# Extrudrboard2.net
KiCad netlist of a schematic drawn in EAGLE
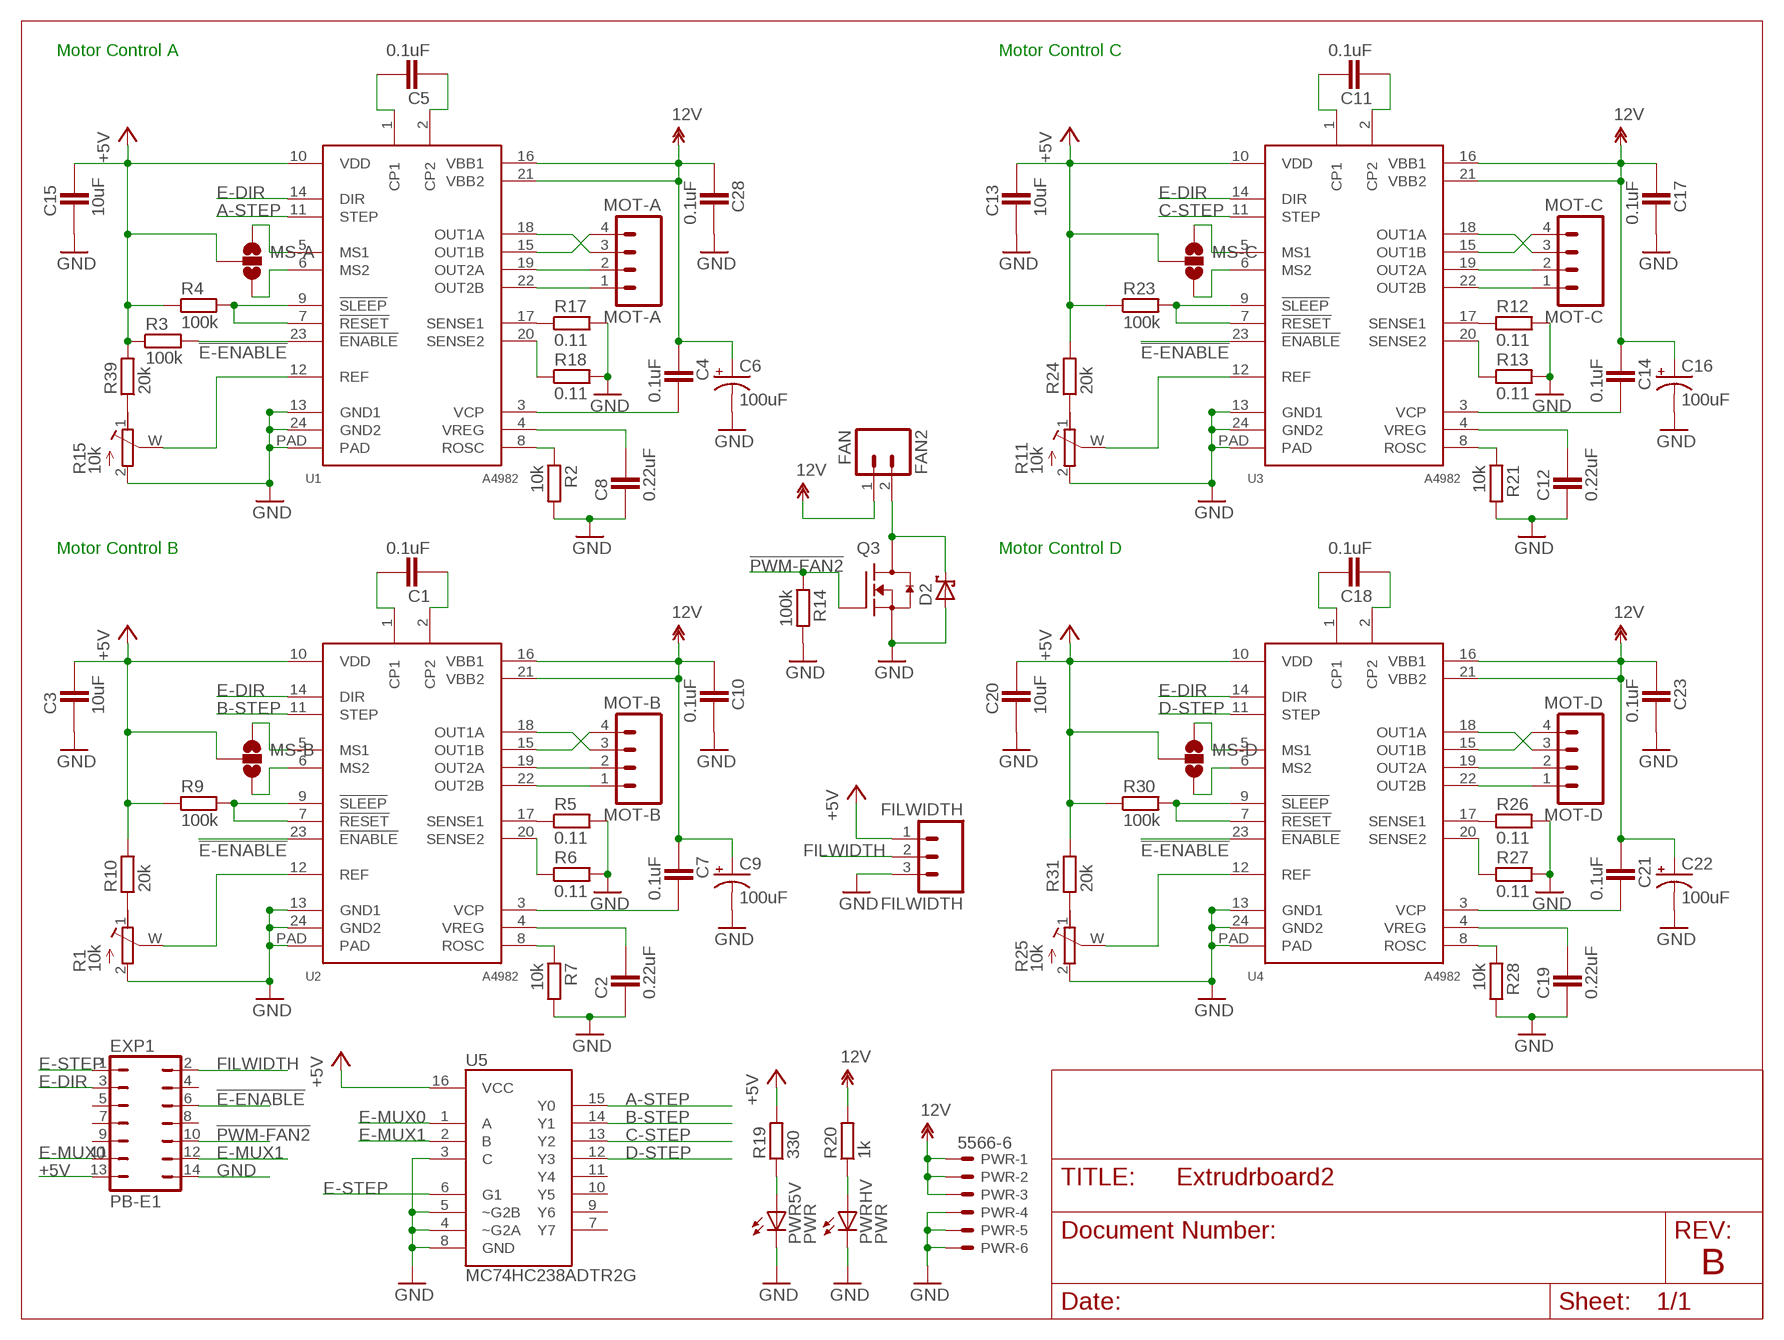
[diagram p0: schematic, sheet 1]

(export (version "E")
  (design (tool "Eeschema 10.0.6"))
  (components
    (comp (ref "C1")
      (value "0.1uF")
      (footprint "eagle-import:CAPC2012X145AN")
      (libsource (lib "eagle-import") (part "CAPACITOR_0805"))
    )
    (comp (ref "C2")
      (value "0.22uF")
      (footprint "eagle-import:CAPC2012X145AN")
      (libsource (lib "eagle-import") (part "CAPACITOR_0805"))
    )
    (comp (ref "C3")
      (value "10uF")
      (footprint "eagle-import:CAPC2012X145AN")
      (libsource (lib "eagle-import") (part "CAPACITOR_0805"))
    )
    (comp (ref "C4")
      (value "0.1uF")
      (footprint "eagle-import:CAPC2012X145AN")
      (libsource (lib "eagle-import") (part "CAPACITOR_0805"))
    )
    (comp (ref "C5")
      (value "0.1uF")
      (footprint "eagle-import:CAPC2012X145AN")
      (libsource (lib "eagle-import") (part "CAPACITOR_0805"))
    )
    (comp (ref "C6")
      (value "100uF")
      (footprint "eagle-import:PANASONIC_D")
      (libsource (lib "eagle-import") (part "CPOL-USD"))
    )
    (comp (ref "C7")
      (value "0.1uF")
      (footprint "eagle-import:CAPC2012X145AN")
      (libsource (lib "eagle-import") (part "CAPACITOR_0805"))
    )
    (comp (ref "C8")
      (value "0.22uF")
      (footprint "eagle-import:CAPC2012X145AN")
      (libsource (lib "eagle-import") (part "CAPACITOR_0805"))
    )
    (comp (ref "C9")
      (value "100uF")
      (footprint "eagle-import:PANASONIC_D")
      (libsource (lib "eagle-import") (part "CPOL-USD"))
    )
    (comp (ref "C10")
      (value "0.1uF")
      (footprint "eagle-import:CAPC2012X145AN")
      (libsource (lib "eagle-import") (part "CAPACITOR_0805"))
    )
    (comp (ref "C11")
      (value "0.1uF")
      (footprint "eagle-import:CAPC2012X145AN")
      (libsource (lib "eagle-import") (part "CAPACITOR_0805"))
    )
    (comp (ref "C12")
      (value "0.22uF")
      (footprint "eagle-import:CAPC2012X145AN")
      (libsource (lib "eagle-import") (part "CAPACITOR_0805"))
    )
    (comp (ref "C13")
      (value "10uF")
      (footprint "eagle-import:CAPC2012X145AN")
      (libsource (lib "eagle-import") (part "CAPACITOR_0805"))
    )
    (comp (ref "C14")
      (value "0.1uF")
      (footprint "eagle-import:CAPC2012X145AN")
      (libsource (lib "eagle-import") (part "CAPACITOR_0805"))
    )
    (comp (ref "C15")
      (value "10uF")
      (footprint "eagle-import:CAPC2012X145AN")
      (libsource (lib "eagle-import") (part "CAPACITOR_0805"))
    )
    (comp (ref "C16")
      (value "100uF")
      (footprint "eagle-import:PANASONIC_D")
      (libsource (lib "eagle-import") (part "CPOL-USD"))
    )
    (comp (ref "C17")
      (value "0.1uF")
      (footprint "eagle-import:CAPC2012X145AN")
      (libsource (lib "eagle-import") (part "CAPACITOR_0805"))
    )
    (comp (ref "C18")
      (value "0.1uF")
      (footprint "eagle-import:CAPC2012X145AN")
      (libsource (lib "eagle-import") (part "CAPACITOR_0805"))
    )
    (comp (ref "C19")
      (value "0.22uF")
      (footprint "eagle-import:CAPC2012X145AN")
      (libsource (lib "eagle-import") (part "CAPACITOR_0805"))
    )
    (comp (ref "C20")
      (value "10uF")
      (footprint "eagle-import:CAPC2012X145AN")
      (libsource (lib "eagle-import") (part "CAPACITOR_0805"))
    )
    (comp (ref "C21")
      (value "0.1uF")
      (footprint "eagle-import:CAPC2012X145AN")
      (libsource (lib "eagle-import") (part "CAPACITOR_0805"))
    )
    (comp (ref "C22")
      (value "100uF")
      (footprint "eagle-import:PANASONIC_D")
      (libsource (lib "eagle-import") (part "CPOL-USD"))
    )
    (comp (ref "C23")
      (value "0.1uF")
      (footprint "eagle-import:CAPC2012X145AN")
      (libsource (lib "eagle-import") (part "CAPACITOR_0805"))
    )
    (comp (ref "C28")
      (value "0.1uF")
      (footprint "eagle-import:CAPC2012X145AN")
      (libsource (lib "eagle-import") (part "CAPACITOR_0805"))
    )
    (comp (ref "D2")
      (value "SCH-DIODESMA")
      (footprint "eagle-import:SMA")
      (libsource (lib "eagle-import") (part "SCH-DIODESMA"))
    )
    (comp (ref "EXP1")
      (value "PB-E1")
      (footprint "eagle-import:JP7Q")
      (libsource (lib "eagle-import") (part "JP7Q"))
    )
    (comp (ref "FAN2")
      (value "FAN")
      (footprint "eagle-import:1X02")
      (libsource (lib "eagle-import") (part "M02PTH"))
    )
    (comp (ref "FILWIDTH")
      (value "FILWIDTH")
      (footprint "eagle-import:1X03")
      (libsource (lib "eagle-import") (part "M03PTH"))
    )
    (comp (ref "MOT-A")
      (value "MOT-A")
      (footprint "eagle-import:MOLEX-1X4")
      (libsource (lib "eagle-import") (part "M04POLAR"))
    )
    (comp (ref "MOT-B")
      (value "MOT-B")
      (footprint "eagle-import:MOLEX-1X4")
      (libsource (lib "eagle-import") (part "M04POLAR"))
    )
    (comp (ref "MOT-C")
      (value "MOT-C")
      (footprint "eagle-import:MOLEX-1X4")
      (libsource (lib "eagle-import") (part "M04POLAR"))
    )
    (comp (ref "MOT-D")
      (value "MOT-D")
      (footprint "eagle-import:MOLEX-1X4")
      (libsource (lib "eagle-import") (part "M04POLAR"))
    )
    (comp (ref "MS-A")
      (value "SOLDERJUMPER_2WAYCONNECTED")
      (footprint "eagle-import:SJ_3_CONNECTED")
      (libsource (lib "eagle-import") (part "SOLDERJUMPER_2WAYCONNECTED"))
    )
    (comp (ref "MS-B")
      (value "SOLDERJUMPER_2WAYCONNECTED")
      (footprint "eagle-import:SJ_3_CONNECTED")
      (libsource (lib "eagle-import") (part "SOLDERJUMPER_2WAYCONNECTED"))
    )
    (comp (ref "MS-C")
      (value "SOLDERJUMPER_2WAYCONNECTED")
      (footprint "eagle-import:SJ_3_CONNECTED")
      (libsource (lib "eagle-import") (part "SOLDERJUMPER_2WAYCONNECTED"))
    )
    (comp (ref "MS-D")
      (value "SOLDERJUMPER_2WAYCONNECTED")
      (footprint "eagle-import:SJ_3_CONNECTED")
      (libsource (lib "eagle-import") (part "SOLDERJUMPER_2WAYCONNECTED"))
    )
    (comp (ref "PWR")
      (value "5566-6")
      (footprint "eagle-import:5566-6")
      (fields (field (name "MPN") "95566-61002"))
      (libsource (lib "eagle-import") (part "5566-6"))
    )
    (comp (ref "PWR5V")
      (value "PWR")
      (footprint "eagle-import:CHIP-LED0805")
      (libsource (lib "eagle-import") (part "LEDCHIP-LED0805"))
    )
    (comp (ref "PWRHV")
      (value "PWR")
      (footprint "eagle-import:CHIP-LED0805")
      (libsource (lib "eagle-import") (part "LEDCHIP-LED0805"))
    )
    (comp (ref "Q3")
      (value "RFP30N06LE")
      (footprint "eagle-import:SOT95P280X135-3N")
      (libsource (lib "eagle-import") (part "MOSFET-NCH_SOT-23"))
    )
    (comp (ref "R1")
      (value "10k")
      (footprint "eagle-import:RTRIM-ST4ETB")
      (libsource (lib "eagle-import") (part "RTRIM-ST-4EA"))
    )
    (comp (ref "R2")
      (value "10k")
      (footprint "eagle-import:RESC2012X70N")
      (libsource (lib "eagle-import") (part "RESISTOR_0805"))
    )
    (comp (ref "R3")
      (value "100k")
      (footprint "eagle-import:RESC2012X70N")
      (libsource (lib "eagle-import") (part "RESISTOR_0805"))
    )
    (comp (ref "R4")
      (value "100k")
      (footprint "eagle-import:RESC2012X70N")
      (libsource (lib "eagle-import") (part "RESISTOR_0805"))
    )
    (comp (ref "R5")
      (value "0.11")
      (footprint "eagle-import:RESC2012X70N")
      (libsource (lib "eagle-import") (part "RESISTOR_0805"))
    )
    (comp (ref "R6")
      (value "0.11")
      (footprint "eagle-import:RESC2012X70N")
      (libsource (lib "eagle-import") (part "RESISTOR_0805"))
    )
    (comp (ref "R7")
      (value "10k")
      (footprint "eagle-import:RESC2012X70N")
      (libsource (lib "eagle-import") (part "RESISTOR_0805"))
    )
    (comp (ref "R9")
      (value "100k")
      (footprint "eagle-import:RESC2012X70N")
      (libsource (lib "eagle-import") (part "RESISTOR_0805"))
    )
    (comp (ref "R10")
      (value "20k")
      (footprint "eagle-import:RESC2012X70N")
      (libsource (lib "eagle-import") (part "RESISTOR_0805"))
    )
    (comp (ref "R11")
      (value "10k")
      (footprint "eagle-import:RTRIM-ST4ETB")
      (libsource (lib "eagle-import") (part "RTRIM-ST-4EA"))
    )
    (comp (ref "R12")
      (value "0.11")
      (footprint "eagle-import:RESC2012X70N")
      (libsource (lib "eagle-import") (part "RESISTOR_0805"))
    )
    (comp (ref "R13")
      (value "0.11")
      (footprint "eagle-import:RESC2012X70N")
      (libsource (lib "eagle-import") (part "RESISTOR_0805"))
    )
    (comp (ref "R14")
      (value "100k")
      (footprint "eagle-import:RESC2012X70N")
      (libsource (lib "eagle-import") (part "RESISTOR_0805"))
    )
    (comp (ref "R15")
      (value "10k")
      (footprint "eagle-import:RTRIM-ST4ETB")
      (libsource (lib "eagle-import") (part "RTRIM-ST-4EA"))
    )
    (comp (ref "R17")
      (value "0.11")
      (footprint "eagle-import:RESC2012X70N")
      (libsource (lib "eagle-import") (part "RESISTOR_0805"))
    )
    (comp (ref "R18")
      (value "0.11")
      (footprint "eagle-import:RESC2012X70N")
      (libsource (lib "eagle-import") (part "RESISTOR_0805"))
    )
    (comp (ref "R19")
      (value "330")
      (footprint "eagle-import:RESC2012X70N")
      (libsource (lib "eagle-import") (part "RESISTOR_0805"))
    )
    (comp (ref "R20")
      (value "1k")
      (footprint "eagle-import:RESC2012X70N")
      (libsource (lib "eagle-import") (part "RESISTOR_0805"))
    )
    (comp (ref "R21")
      (value "10k")
      (footprint "eagle-import:RESC2012X70N")
      (libsource (lib "eagle-import") (part "RESISTOR_0805"))
    )
    (comp (ref "R23")
      (value "100k")
      (footprint "eagle-import:RESC2012X70N")
      (libsource (lib "eagle-import") (part "RESISTOR_0805"))
    )
    (comp (ref "R24")
      (value "20k")
      (footprint "eagle-import:RESC2012X70N")
      (libsource (lib "eagle-import") (part "RESISTOR_0805"))
    )
    (comp (ref "R25")
      (value "10k")
      (footprint "eagle-import:RTRIM-ST4ETB")
      (libsource (lib "eagle-import") (part "RTRIM-ST-4EA"))
    )
    (comp (ref "R26")
      (value "0.11")
      (footprint "eagle-import:RESC2012X70N")
      (libsource (lib "eagle-import") (part "RESISTOR_0805"))
    )
    (comp (ref "R27")
      (value "0.11")
      (footprint "eagle-import:RESC2012X70N")
      (libsource (lib "eagle-import") (part "RESISTOR_0805"))
    )
    (comp (ref "R28")
      (value "10k")
      (footprint "eagle-import:RESC2012X70N")
      (libsource (lib "eagle-import") (part "RESISTOR_0805"))
    )
    (comp (ref "R30")
      (value "100k")
      (footprint "eagle-import:RESC2012X70N")
      (libsource (lib "eagle-import") (part "RESISTOR_0805"))
    )
    (comp (ref "R31")
      (value "20k")
      (footprint "eagle-import:RESC2012X70N")
      (libsource (lib "eagle-import") (part "RESISTOR_0805"))
    )
    (comp (ref "R39")
      (value "20k")
      (footprint "eagle-import:RESC2012X70N")
      (libsource (lib "eagle-import") (part "RESISTOR_0805"))
    )
    (comp (ref "U1")
      (value "A4982")
      (footprint "eagle-import:TSSOP-24")
      (libsource (lib "eagle-import") (part "A4982"))
    )
    (comp (ref "U2")
      (value "A4982")
      (footprint "eagle-import:TSSOP-24")
      (libsource (lib "eagle-import") (part "A4982"))
    )
    (comp (ref "U3")
      (value "A4982")
      (footprint "eagle-import:TSSOP-24")
      (libsource (lib "eagle-import") (part "A4982"))
    )
    (comp (ref "U4")
      (value "A4982")
      (footprint "eagle-import:TSSOP-24")
      (libsource (lib "eagle-import") (part "A4982"))
    )
    (comp (ref "U5")
      (value "MC74HC238ADTR2G")
      (footprint "eagle-import:TSSOP16")
      (libsource (lib "eagle-import") (part "M74HC238DT"))
    )
  )
  (nets
    (net (code "1") (name "+5V") (class "Default")
      (node (ref "C13") (pin "2") (pinfunction "2_2") (pintype "passive"))
      (node (ref "C15") (pin "2") (pinfunction "2_2") (pintype "passive"))
      (node (ref "C20") (pin "2") (pinfunction "2_2") (pintype "passive"))
      (node (ref "C3") (pin "2") (pinfunction "2_2") (pintype "passive"))
      (node (ref "EXP1") (pin "13") (pinfunction "13_13") (pintype "passive"))
      (node (ref "FILWIDTH") (pin "1") (pinfunction "1_1") (pintype "passive"))
      (node (ref "MS-A") (pin "2") (pinfunction "2_2") (pintype "passive"))
      (node (ref "MS-B") (pin "2") (pinfunction "2_2") (pintype "passive"))
      (node (ref "MS-C") (pin "2") (pinfunction "2_2") (pintype "passive"))
      (node (ref "MS-D") (pin "2") (pinfunction "2_2") (pintype "passive"))
      (node (ref "R10") (pin "2") (pinfunction "2_2") (pintype "passive"))
      (node (ref "R19") (pin "2") (pinfunction "2_2") (pintype "passive"))
      (node (ref "R23") (pin "1") (pinfunction "1_1") (pintype "passive"))
      (node (ref "R24") (pin "2") (pinfunction "2_2") (pintype "passive"))
      (node (ref "R3") (pin "1") (pinfunction "1_1") (pintype "passive"))
      (node (ref "R30") (pin "1") (pinfunction "1_1") (pintype "passive"))
      (node (ref "R31") (pin "2") (pinfunction "2_2") (pintype "passive"))
      (node (ref "R39") (pin "2") (pinfunction "2_2") (pintype "passive"))
      (node (ref "R4") (pin "1") (pinfunction "1_1") (pintype "passive"))
      (node (ref "R9") (pin "1") (pinfunction "1_1") (pintype "passive"))
      (node (ref "U1") (pin "10") (pinfunction "VDD_10") (pintype "power_in"))
      (node (ref "U2") (pin "10") (pinfunction "VDD_10") (pintype "power_in"))
      (node (ref "U3") (pin "10") (pinfunction "VDD_10") (pintype "power_in"))
      (node (ref "U4") (pin "10") (pinfunction "VDD_10") (pintype "power_in"))
      (node (ref "U5") (pin "16") (pinfunction "VCC_16") (pintype "bidirectional"))
    )
    (net (code "2") (name "/A-STEP") (class "Default")
      (node (ref "U1") (pin "11") (pinfunction "STEP_11") (pintype "input"))
      (node (ref "U5") (pin "15") (pinfunction "Y0_15") (pintype "bidirectional"))
    )
    (net (code "3") (name "/B-STEP") (class "Default")
      (node (ref "U2") (pin "11") (pinfunction "STEP_11") (pintype "input"))
      (node (ref "U5") (pin "14") (pinfunction "Y1_14") (pintype "bidirectional"))
    )
    (net (code "4") (name "/C-STEP") (class "Default")
      (node (ref "U3") (pin "11") (pinfunction "STEP_11") (pintype "input"))
      (node (ref "U5") (pin "13") (pinfunction "Y2_13") (pintype "bidirectional"))
    )
    (net (code "5") (name "/D-STEP") (class "Default")
      (node (ref "U4") (pin "11") (pinfunction "STEP_11") (pintype "input"))
      (node (ref "U5") (pin "12") (pinfunction "Y3_12") (pintype "bidirectional"))
    )
    (net (code "6") (name "/E-DIR") (class "Default")
      (node (ref "EXP1") (pin "3") (pinfunction "3_3") (pintype "passive"))
      (node (ref "U1") (pin "14") (pinfunction "DIR_14") (pintype "input"))
      (node (ref "U2") (pin "14") (pinfunction "DIR_14") (pintype "input"))
      (node (ref "U3") (pin "14") (pinfunction "DIR_14") (pintype "input"))
      (node (ref "U4") (pin "14") (pinfunction "DIR_14") (pintype "input"))
    )
    (net (code "7") (name "/E-MUX0") (class "Default")
      (node (ref "EXP1") (pin "11") (pinfunction "11_11") (pintype "passive"))
      (node (ref "U5") (pin "1") (pinfunction "A_1") (pintype "bidirectional"))
    )
    (net (code "8") (name "/E-MUX1") (class "Default")
      (node (ref "EXP1") (pin "12") (pinfunction "12_12") (pintype "passive"))
      (node (ref "U5") (pin "2") (pinfunction "B_2") (pintype "bidirectional"))
    )
    (net (code "9") (name "/E-STEP") (class "Default")
      (node (ref "EXP1") (pin "1") (pinfunction "1_1") (pintype "passive"))
      (node (ref "U5") (pin "6") (pinfunction "G1_6") (pintype "bidirectional"))
    )
    (net (code "10") (name "/FILWIDTH") (class "Default")
      (node (ref "EXP1") (pin "2") (pinfunction "2_2") (pintype "passive"))
      (node (ref "FILWIDTH") (pin "2") (pinfunction "2_2") (pintype "passive"))
    )
    (net (code "11") (name "/~{E-ENABLE}") (class "Default")
      (node (ref "EXP1") (pin "6") (pinfunction "6_6") (pintype "passive"))
      (node (ref "R3") (pin "2") (pinfunction "2_2") (pintype "passive"))
      (node (ref "U1") (pin "23") (pinfunction "~{ENABLE}_23") (pintype "input"))
      (node (ref "U2") (pin "23") (pinfunction "~{ENABLE}_23") (pintype "input"))
      (node (ref "U3") (pin "23") (pinfunction "~{ENABLE}_23") (pintype "input"))
      (node (ref "U4") (pin "23") (pinfunction "~{ENABLE}_23") (pintype "input"))
    )
    (net (code "12") (name "/~{PWM-FAN2}") (class "Default")
      (node (ref "EXP1") (pin "10") (pinfunction "10_10") (pintype "passive"))
      (node (ref "Q3") (pin "1") (pinfunction "G_1") (pintype "passive"))
      (node (ref "R14") (pin "1") (pinfunction "1_1") (pintype "passive"))
    )
    (net (code "13") (name "12V") (class "Default")
      (node (ref "C10") (pin "1") (pinfunction "1_1") (pintype "passive"))
      (node (ref "C14") (pin "1") (pinfunction "1_1") (pintype "passive"))
      (node (ref "C16") (pin "+") (pinfunction "+_+") (pintype "passive"))
      (node (ref "C17") (pin "1") (pinfunction "1_1") (pintype "passive"))
      (node (ref "C21") (pin "1") (pinfunction "1_1") (pintype "passive"))
      (node (ref "C22") (pin "+") (pinfunction "+_+") (pintype "passive"))
      (node (ref "C23") (pin "1") (pinfunction "1_1") (pintype "passive"))
      (node (ref "C28") (pin "1") (pinfunction "1_1") (pintype "passive"))
      (node (ref "C4") (pin "1") (pinfunction "1_1") (pintype "passive"))
      (node (ref "C6") (pin "+") (pinfunction "+_+") (pintype "passive"))
      (node (ref "C7") (pin "1") (pinfunction "1_1") (pintype "passive"))
      (node (ref "C9") (pin "+") (pinfunction "+_+") (pintype "passive"))
      (node (ref "FAN2") (pin "1") (pinfunction "1_1") (pintype "passive"))
      (node (ref "PWR") (pin "1") (pinfunction "S_1") (pintype "passive"))
      (node (ref "PWR") (pin "2") (pinfunction "S_2") (pintype "passive"))
      (node (ref "PWR") (pin "3") (pinfunction "S_3") (pintype "passive"))
      (node (ref "R20") (pin "2") (pinfunction "2_2") (pintype "passive"))
      (node (ref "U1") (pin "16") (pinfunction "VBB1_16") (pintype "power_in"))
      (node (ref "U1") (pin "21") (pinfunction "VBB2_21") (pintype "power_in"))
      (node (ref "U2") (pin "16") (pinfunction "VBB1_16") (pintype "power_in"))
      (node (ref "U2") (pin "21") (pinfunction "VBB2_21") (pintype "power_in"))
      (node (ref "U3") (pin "16") (pinfunction "VBB1_16") (pintype "power_in"))
      (node (ref "U3") (pin "21") (pinfunction "VBB2_21") (pintype "power_in"))
      (node (ref "U4") (pin "16") (pinfunction "VBB1_16") (pintype "power_in"))
      (node (ref "U4") (pin "21") (pinfunction "VBB2_21") (pintype "power_in"))
    )
    (net (code "14") (name "GND") (class "Default")
      (node (ref "C10") (pin "2") (pinfunction "2_2") (pintype "passive"))
      (node (ref "C12") (pin "1") (pinfunction "1_1") (pintype "passive"))
      (node (ref "C13") (pin "1") (pinfunction "1_1") (pintype "passive"))
      (node (ref "C15") (pin "1") (pinfunction "1_1") (pintype "passive"))
      (node (ref "C16") (pin "-") (pinfunction "-_-") (pintype "passive"))
      (node (ref "C17") (pin "2") (pinfunction "2_2") (pintype "passive"))
      (node (ref "C19") (pin "1") (pinfunction "1_1") (pintype "passive"))
      (node (ref "C2") (pin "1") (pinfunction "1_1") (pintype "passive"))
      (node (ref "C20") (pin "1") (pinfunction "1_1") (pintype "passive"))
      (node (ref "C22") (pin "-") (pinfunction "-_-") (pintype "passive"))
      (node (ref "C23") (pin "2") (pinfunction "2_2") (pintype "passive"))
      (node (ref "C28") (pin "2") (pinfunction "2_2") (pintype "passive"))
      (node (ref "C3") (pin "1") (pinfunction "1_1") (pintype "passive"))
      (node (ref "C6") (pin "-") (pinfunction "-_-") (pintype "passive"))
      (node (ref "C8") (pin "1") (pinfunction "1_1") (pintype "passive"))
      (node (ref "C9") (pin "-") (pinfunction "-_-") (pintype "passive"))
      (node (ref "D2") (pin "A") (pinfunction "A_A") (pintype "passive"))
      (node (ref "EXP1") (pin "14") (pinfunction "14_14") (pintype "passive"))
      (node (ref "FILWIDTH") (pin "3") (pinfunction "3_3") (pintype "passive"))
      (node (ref "PWR") (pin "4") (pinfunction "S_4") (pintype "passive"))
      (node (ref "PWR") (pin "5") (pinfunction "S_5") (pintype "passive"))
      (node (ref "PWR") (pin "6") (pinfunction "S_6") (pintype "passive"))
      (node (ref "PWR5V") (pin "C") (pinfunction "C_C") (pintype "passive"))
      (node (ref "PWRHV") (pin "C") (pinfunction "C_C") (pintype "passive"))
      (node (ref "Q3") (pin "2") (pinfunction "S_2") (pintype "passive"))
      (node (ref "R1") (pin "2") (pinfunction "E_2") (pintype "passive"))
      (node (ref "R11") (pin "2") (pinfunction "E_2") (pintype "passive"))
      (node (ref "R12") (pin "2") (pinfunction "2_2") (pintype "passive"))
      (node (ref "R13") (pin "2") (pinfunction "2_2") (pintype "passive"))
      (node (ref "R14") (pin "2") (pinfunction "2_2") (pintype "passive"))
      (node (ref "R15") (pin "2") (pinfunction "E_2") (pintype "passive"))
      (node (ref "R17") (pin "2") (pinfunction "2_2") (pintype "passive"))
      (node (ref "R18") (pin "2") (pinfunction "2_2") (pintype "passive"))
      (node (ref "R2") (pin "2") (pinfunction "2_2") (pintype "passive"))
      (node (ref "R21") (pin "2") (pinfunction "2_2") (pintype "passive"))
      (node (ref "R25") (pin "2") (pinfunction "E_2") (pintype "passive"))
      (node (ref "R26") (pin "2") (pinfunction "2_2") (pintype "passive"))
      (node (ref "R27") (pin "2") (pinfunction "2_2") (pintype "passive"))
      (node (ref "R28") (pin "2") (pinfunction "2_2") (pintype "passive"))
      (node (ref "R5") (pin "2") (pinfunction "2_2") (pintype "passive"))
      (node (ref "R6") (pin "2") (pinfunction "2_2") (pintype "passive"))
      (node (ref "R7") (pin "2") (pinfunction "2_2") (pintype "passive"))
      (node (ref "U1") (pin "13") (pinfunction "GND1_13") (pintype "power_in"))
      (node (ref "U1") (pin "24") (pinfunction "GND2_24") (pintype "power_in"))
      (node (ref "U1") (pin "PAD") (pinfunction "PAD_PAD") (pintype "power_in"))
      (node (ref "U2") (pin "13") (pinfunction "GND1_13") (pintype "power_in"))
      (node (ref "U2") (pin "24") (pinfunction "GND2_24") (pintype "power_in"))
      (node (ref "U2") (pin "PAD") (pinfunction "PAD_PAD") (pintype "power_in"))
      (node (ref "U3") (pin "13") (pinfunction "GND1_13") (pintype "power_in"))
      (node (ref "U3") (pin "24") (pinfunction "GND2_24") (pintype "power_in"))
      (node (ref "U3") (pin "PAD") (pinfunction "PAD_PAD") (pintype "power_in"))
      (node (ref "U4") (pin "13") (pinfunction "GND1_13") (pintype "power_in"))
      (node (ref "U4") (pin "24") (pinfunction "GND2_24") (pintype "power_in"))
      (node (ref "U4") (pin "PAD") (pinfunction "PAD_PAD") (pintype "power_in"))
      (node (ref "U5") (pin "3") (pinfunction "C_3") (pintype "bidirectional"))
      (node (ref "U5") (pin "4") (pinfunction "~{G2A}_4") (pintype "bidirectional"))
      (node (ref "U5") (pin "5") (pinfunction "~{G2B}_5") (pintype "bidirectional"))
      (node (ref "U5") (pin "8") (pinfunction "GND_8") (pintype "bidirectional"))
    )
    (net (code "15") (name "Net-(PWR5V-PadA)") (class "Default")
      (node (ref "PWR5V") (pin "A") (pinfunction "A_A") (pintype "passive"))
      (node (ref "R19") (pin "1") (pinfunction "1_1") (pintype "passive"))
    )
    (net (code "16") (name "Net-(PWRHV-PadA)") (class "Default")
      (node (ref "PWRHV") (pin "A") (pinfunction "A_A") (pintype "passive"))
      (node (ref "R20") (pin "1") (pinfunction "1_1") (pintype "passive"))
    )
    (net (code "17") (name "Net-(Q3-D)") (class "Default")
      (node (ref "D2") (pin "C") (pinfunction "C_C") (pintype "passive"))
      (node (ref "FAN2") (pin "2") (pinfunction "2_2") (pintype "passive"))
      (node (ref "Q3") (pin "3") (pinfunction "D_3") (pintype "passive"))
    )
    (net (code "18") (name "Net-(R1-A)") (class "Default")
      (node (ref "R1") (pin "1") (pinfunction "A_1") (pintype "passive"))
      (node (ref "R10") (pin "1") (pinfunction "1_1") (pintype "passive"))
    )
    (net (code "19") (name "Net-(R1-S)") (class "Default")
      (node (ref "R1") (pin "W") (pinfunction "S_W") (pintype "passive"))
      (node (ref "U2") (pin "12") (pinfunction "REF_12") (pintype "input"))
    )
    (net (code "20") (name "Net-(R11-A)") (class "Default")
      (node (ref "R11") (pin "1") (pinfunction "A_1") (pintype "passive"))
      (node (ref "R24") (pin "1") (pinfunction "1_1") (pintype "passive"))
    )
    (net (code "21") (name "Net-(R11-S)") (class "Default")
      (node (ref "R11") (pin "W") (pinfunction "S_W") (pintype "passive"))
      (node (ref "U3") (pin "12") (pinfunction "REF_12") (pintype "input"))
    )
    (net (code "22") (name "Net-(R15-A)") (class "Default")
      (node (ref "R15") (pin "1") (pinfunction "A_1") (pintype "passive"))
      (node (ref "R39") (pin "1") (pinfunction "1_1") (pintype "passive"))
    )
    (net (code "23") (name "Net-(R15-S)") (class "Default")
      (node (ref "R15") (pin "W") (pinfunction "S_W") (pintype "passive"))
      (node (ref "U1") (pin "12") (pinfunction "REF_12") (pintype "input"))
    )
    (net (code "24") (name "Net-(R25-A)") (class "Default")
      (node (ref "R25") (pin "1") (pinfunction "A_1") (pintype "passive"))
      (node (ref "R31") (pin "1") (pinfunction "1_1") (pintype "passive"))
    )
    (net (code "25") (name "Net-(R25-S)") (class "Default")
      (node (ref "R25") (pin "W") (pinfunction "S_W") (pintype "passive"))
      (node (ref "U4") (pin "12") (pinfunction "REF_12") (pintype "input"))
    )
    (net (code "26") (name "Net-(U1-CP1)") (class "Default")
      (node (ref "C5") (pin "2") (pinfunction "2_2") (pintype "passive"))
      (node (ref "U1") (pin "1") (pinfunction "CP1_1") (pintype "passive"))
    )
    (net (code "27") (name "Net-(U1-CP2)") (class "Default")
      (node (ref "C5") (pin "1") (pinfunction "1_1") (pintype "passive"))
      (node (ref "U1") (pin "2") (pinfunction "CP2_2") (pintype "passive"))
    )
    (net (code "28") (name "Net-(U1-MS1)") (class "Default")
      (node (ref "MS-A") (pin "1") (pinfunction "1_1") (pintype "passive"))
      (node (ref "U1") (pin "5") (pinfunction "MS1_5") (pintype "input"))
    )
    (net (code "29") (name "Net-(U1-MS2)") (class "Default")
      (node (ref "MS-A") (pin "3") (pinfunction "3_3") (pintype "passive"))
      (node (ref "U1") (pin "6") (pinfunction "MS2_6") (pintype "input"))
    )
    (net (code "30") (name "Net-(U1-OUT1A)") (class "Default")
      (node (ref "MOT-A") (pin "3") (pinfunction "3_3") (pintype "passive"))
      (node (ref "U1") (pin "18") (pinfunction "OUT1A_18") (pintype "output"))
    )
    (net (code "31") (name "Net-(U1-OUT1B)") (class "Default")
      (node (ref "MOT-A") (pin "4") (pinfunction "4_4") (pintype "passive"))
      (node (ref "U1") (pin "15") (pinfunction "OUT1B_15") (pintype "output"))
    )
    (net (code "32") (name "Net-(U1-OUT2A)") (class "Default")
      (node (ref "MOT-A") (pin "2") (pinfunction "2_2") (pintype "passive"))
      (node (ref "U1") (pin "19") (pinfunction "OUT2A_19") (pintype "output"))
    )
    (net (code "33") (name "Net-(U1-OUT2B)") (class "Default")
      (node (ref "MOT-A") (pin "1") (pinfunction "1_1") (pintype "passive"))
      (node (ref "U1") (pin "22") (pinfunction "OUT2B_22") (pintype "output"))
    )
    (net (code "34") (name "Net-(U1-ROSC)") (class "Default")
      (node (ref "R2") (pin "1") (pinfunction "1_1") (pintype "passive"))
      (node (ref "U1") (pin "8") (pinfunction "ROSC_8") (pintype "passive"))
    )
    (net (code "35") (name "Net-(U1-SENSE1)") (class "Default")
      (node (ref "R17") (pin "1") (pinfunction "1_1") (pintype "passive"))
      (node (ref "U1") (pin "17") (pinfunction "SENSE1_17") (pintype "passive"))
    )
    (net (code "36") (name "Net-(U1-SENSE2)") (class "Default")
      (node (ref "R18") (pin "1") (pinfunction "1_1") (pintype "passive"))
      (node (ref "U1") (pin "20") (pinfunction "SENSE2_20") (pintype "passive"))
    )
    (net (code "37") (name "Net-(U1-VCP)") (class "Default")
      (node (ref "C4") (pin "2") (pinfunction "2_2") (pintype "passive"))
      (node (ref "U1") (pin "3") (pinfunction "VCP_3") (pintype "passive"))
    )
    (net (code "38") (name "Net-(U1-VREG)") (class "Default")
      (node (ref "C8") (pin "2") (pinfunction "2_2") (pintype "passive"))
      (node (ref "U1") (pin "4") (pinfunction "VREG_4") (pintype "passive"))
    )
    (net (code "39") (name "Net-(U1-~{RESET})") (class "Default")
      (node (ref "R4") (pin "2") (pinfunction "2_2") (pintype "passive"))
      (node (ref "U1") (pin "7") (pinfunction "~{RESET}_7") (pintype "input"))
      (node (ref "U1") (pin "9") (pinfunction "~{SLEEP}_9") (pintype "input"))
    )
    (net (code "40") (name "Net-(U2-CP1)") (class "Default")
      (node (ref "C1") (pin "2") (pinfunction "2_2") (pintype "passive"))
      (node (ref "U2") (pin "1") (pinfunction "CP1_1") (pintype "passive"))
    )
    (net (code "41") (name "Net-(U2-CP2)") (class "Default")
      (node (ref "C1") (pin "1") (pinfunction "1_1") (pintype "passive"))
      (node (ref "U2") (pin "2") (pinfunction "CP2_2") (pintype "passive"))
    )
    (net (code "42") (name "Net-(U2-MS1)") (class "Default")
      (node (ref "MS-B") (pin "1") (pinfunction "1_1") (pintype "passive"))
      (node (ref "U2") (pin "5") (pinfunction "MS1_5") (pintype "input"))
    )
    (net (code "43") (name "Net-(U2-MS2)") (class "Default")
      (node (ref "MS-B") (pin "3") (pinfunction "3_3") (pintype "passive"))
      (node (ref "U2") (pin "6") (pinfunction "MS2_6") (pintype "input"))
    )
    (net (code "44") (name "Net-(U2-OUT1A)") (class "Default")
      (node (ref "MOT-B") (pin "3") (pinfunction "3_3") (pintype "passive"))
      (node (ref "U2") (pin "18") (pinfunction "OUT1A_18") (pintype "output"))
    )
    (net (code "45") (name "Net-(U2-OUT1B)") (class "Default")
      (node (ref "MOT-B") (pin "4") (pinfunction "4_4") (pintype "passive"))
      (node (ref "U2") (pin "15") (pinfunction "OUT1B_15") (pintype "output"))
    )
    (net (code "46") (name "Net-(U2-OUT2A)") (class "Default")
      (node (ref "MOT-B") (pin "2") (pinfunction "2_2") (pintype "passive"))
      (node (ref "U2") (pin "19") (pinfunction "OUT2A_19") (pintype "output"))
    )
    (net (code "47") (name "Net-(U2-OUT2B)") (class "Default")
      (node (ref "MOT-B") (pin "1") (pinfunction "1_1") (pintype "passive"))
      (node (ref "U2") (pin "22") (pinfunction "OUT2B_22") (pintype "output"))
    )
    (net (code "48") (name "Net-(U2-ROSC)") (class "Default")
      (node (ref "R7") (pin "1") (pinfunction "1_1") (pintype "passive"))
      (node (ref "U2") (pin "8") (pinfunction "ROSC_8") (pintype "passive"))
    )
    (net (code "49") (name "Net-(U2-SENSE1)") (class "Default")
      (node (ref "R5") (pin "1") (pinfunction "1_1") (pintype "passive"))
      (node (ref "U2") (pin "17") (pinfunction "SENSE1_17") (pintype "passive"))
    )
    (net (code "50") (name "Net-(U2-SENSE2)") (class "Default")
      (node (ref "R6") (pin "1") (pinfunction "1_1") (pintype "passive"))
      (node (ref "U2") (pin "20") (pinfunction "SENSE2_20") (pintype "passive"))
    )
    (net (code "51") (name "Net-(U2-VCP)") (class "Default")
      (node (ref "C7") (pin "2") (pinfunction "2_2") (pintype "passive"))
      (node (ref "U2") (pin "3") (pinfunction "VCP_3") (pintype "passive"))
    )
    (net (code "52") (name "Net-(U2-VREG)") (class "Default")
      (node (ref "C2") (pin "2") (pinfunction "2_2") (pintype "passive"))
      (node (ref "U2") (pin "4") (pinfunction "VREG_4") (pintype "passive"))
    )
    (net (code "53") (name "Net-(U2-~{RESET})") (class "Default")
      (node (ref "R9") (pin "2") (pinfunction "2_2") (pintype "passive"))
      (node (ref "U2") (pin "7") (pinfunction "~{RESET}_7") (pintype "input"))
      (node (ref "U2") (pin "9") (pinfunction "~{SLEEP}_9") (pintype "input"))
    )
    (net (code "54") (name "Net-(U3-CP1)") (class "Default")
      (node (ref "C11") (pin "2") (pinfunction "2_2") (pintype "passive"))
      (node (ref "U3") (pin "1") (pinfunction "CP1_1") (pintype "passive"))
    )
    (net (code "55") (name "Net-(U3-CP2)") (class "Default")
      (node (ref "C11") (pin "1") (pinfunction "1_1") (pintype "passive"))
      (node (ref "U3") (pin "2") (pinfunction "CP2_2") (pintype "passive"))
    )
    (net (code "56") (name "Net-(U3-MS1)") (class "Default")
      (node (ref "MS-C") (pin "1") (pinfunction "1_1") (pintype "passive"))
      (node (ref "U3") (pin "5") (pinfunction "MS1_5") (pintype "input"))
    )
    (net (code "57") (name "Net-(U3-MS2)") (class "Default")
      (node (ref "MS-C") (pin "3") (pinfunction "3_3") (pintype "passive"))
      (node (ref "U3") (pin "6") (pinfunction "MS2_6") (pintype "input"))
    )
    (net (code "58") (name "Net-(U3-OUT1A)") (class "Default")
      (node (ref "MOT-C") (pin "3") (pinfunction "3_3") (pintype "passive"))
      (node (ref "U3") (pin "18") (pinfunction "OUT1A_18") (pintype "output"))
    )
    (net (code "59") (name "Net-(U3-OUT1B)") (class "Default")
      (node (ref "MOT-C") (pin "4") (pinfunction "4_4") (pintype "passive"))
      (node (ref "U3") (pin "15") (pinfunction "OUT1B_15") (pintype "output"))
    )
    (net (code "60") (name "Net-(U3-OUT2A)") (class "Default")
      (node (ref "MOT-C") (pin "2") (pinfunction "2_2") (pintype "passive"))
      (node (ref "U3") (pin "19") (pinfunction "OUT2A_19") (pintype "output"))
    )
    (net (code "61") (name "Net-(U3-OUT2B)") (class "Default")
      (node (ref "MOT-C") (pin "1") (pinfunction "1_1") (pintype "passive"))
      (node (ref "U3") (pin "22") (pinfunction "OUT2B_22") (pintype "output"))
    )
    (net (code "62") (name "Net-(U3-ROSC)") (class "Default")
      (node (ref "R21") (pin "1") (pinfunction "1_1") (pintype "passive"))
      (node (ref "U3") (pin "8") (pinfunction "ROSC_8") (pintype "passive"))
    )
    (net (code "63") (name "Net-(U3-SENSE1)") (class "Default")
      (node (ref "R12") (pin "1") (pinfunction "1_1") (pintype "passive"))
      (node (ref "U3") (pin "17") (pinfunction "SENSE1_17") (pintype "passive"))
    )
    (net (code "64") (name "Net-(U3-SENSE2)") (class "Default")
      (node (ref "R13") (pin "1") (pinfunction "1_1") (pintype "passive"))
      (node (ref "U3") (pin "20") (pinfunction "SENSE2_20") (pintype "passive"))
    )
    (net (code "65") (name "Net-(U3-VCP)") (class "Default")
      (node (ref "C14") (pin "2") (pinfunction "2_2") (pintype "passive"))
      (node (ref "U3") (pin "3") (pinfunction "VCP_3") (pintype "passive"))
    )
    (net (code "66") (name "Net-(U3-VREG)") (class "Default")
      (node (ref "C12") (pin "2") (pinfunction "2_2") (pintype "passive"))
      (node (ref "U3") (pin "4") (pinfunction "VREG_4") (pintype "passive"))
    )
    (net (code "67") (name "Net-(U3-~{RESET})") (class "Default")
      (node (ref "R23") (pin "2") (pinfunction "2_2") (pintype "passive"))
      (node (ref "U3") (pin "7") (pinfunction "~{RESET}_7") (pintype "input"))
      (node (ref "U3") (pin "9") (pinfunction "~{SLEEP}_9") (pintype "input"))
    )
    (net (code "68") (name "Net-(U4-CP1)") (class "Default")
      (node (ref "C18") (pin "2") (pinfunction "2_2") (pintype "passive"))
      (node (ref "U4") (pin "1") (pinfunction "CP1_1") (pintype "passive"))
    )
    (net (code "69") (name "Net-(U4-CP2)") (class "Default")
      (node (ref "C18") (pin "1") (pinfunction "1_1") (pintype "passive"))
      (node (ref "U4") (pin "2") (pinfunction "CP2_2") (pintype "passive"))
    )
    (net (code "70") (name "Net-(U4-MS1)") (class "Default")
      (node (ref "MS-D") (pin "1") (pinfunction "1_1") (pintype "passive"))
      (node (ref "U4") (pin "5") (pinfunction "MS1_5") (pintype "input"))
    )
    (net (code "71") (name "Net-(U4-MS2)") (class "Default")
      (node (ref "MS-D") (pin "3") (pinfunction "3_3") (pintype "passive"))
      (node (ref "U4") (pin "6") (pinfunction "MS2_6") (pintype "input"))
    )
    (net (code "72") (name "Net-(U4-OUT1A)") (class "Default")
      (node (ref "MOT-D") (pin "3") (pinfunction "3_3") (pintype "passive"))
      (node (ref "U4") (pin "18") (pinfunction "OUT1A_18") (pintype "output"))
    )
    (net (code "73") (name "Net-(U4-OUT1B)") (class "Default")
      (node (ref "MOT-D") (pin "4") (pinfunction "4_4") (pintype "passive"))
      (node (ref "U4") (pin "15") (pinfunction "OUT1B_15") (pintype "output"))
    )
    (net (code "74") (name "Net-(U4-OUT2A)") (class "Default")
      (node (ref "MOT-D") (pin "2") (pinfunction "2_2") (pintype "passive"))
      (node (ref "U4") (pin "19") (pinfunction "OUT2A_19") (pintype "output"))
    )
    (net (code "75") (name "Net-(U4-OUT2B)") (class "Default")
      (node (ref "MOT-D") (pin "1") (pinfunction "1_1") (pintype "passive"))
      (node (ref "U4") (pin "22") (pinfunction "OUT2B_22") (pintype "output"))
    )
    (net (code "76") (name "Net-(U4-ROSC)") (class "Default")
      (node (ref "R28") (pin "1") (pinfunction "1_1") (pintype "passive"))
      (node (ref "U4") (pin "8") (pinfunction "ROSC_8") (pintype "passive"))
    )
    (net (code "77") (name "Net-(U4-SENSE1)") (class "Default")
      (node (ref "R26") (pin "1") (pinfunction "1_1") (pintype "passive"))
      (node (ref "U4") (pin "17") (pinfunction "SENSE1_17") (pintype "passive"))
    )
    (net (code "78") (name "Net-(U4-SENSE2)") (class "Default")
      (node (ref "R27") (pin "1") (pinfunction "1_1") (pintype "passive"))
      (node (ref "U4") (pin "20") (pinfunction "SENSE2_20") (pintype "passive"))
    )
    (net (code "79") (name "Net-(U4-VCP)") (class "Default")
      (node (ref "C21") (pin "2") (pinfunction "2_2") (pintype "passive"))
      (node (ref "U4") (pin "3") (pinfunction "VCP_3") (pintype "passive"))
    )
    (net (code "80") (name "Net-(U4-VREG)") (class "Default")
      (node (ref "C19") (pin "2") (pinfunction "2_2") (pintype "passive"))
      (node (ref "U4") (pin "4") (pinfunction "VREG_4") (pintype "passive"))
    )
    (net (code "81") (name "Net-(U4-~{RESET})") (class "Default")
      (node (ref "R30") (pin "2") (pinfunction "2_2") (pintype "passive"))
      (node (ref "U4") (pin "7") (pinfunction "~{RESET}_7") (pintype "input"))
      (node (ref "U4") (pin "9") (pinfunction "~{SLEEP}_9") (pintype "input"))
    )
    (net (code "82") (name "unconnected-(EXP1-Pad4)") (class "Default")
      (node (ref "EXP1") (pin "4") (pinfunction "4_4") (pintype "passive"))
    )
    (net (code "83") (name "unconnected-(EXP1-Pad5)") (class "Default")
      (node (ref "EXP1") (pin "5") (pinfunction "5_5") (pintype "passive"))
    )
    (net (code "84") (name "unconnected-(EXP1-Pad7)") (class "Default")
      (node (ref "EXP1") (pin "7") (pinfunction "7_7") (pintype "passive"))
    )
    (net (code "85") (name "unconnected-(EXP1-Pad8)") (class "Default")
      (node (ref "EXP1") (pin "8") (pinfunction "8_8") (pintype "passive"))
    )
    (net (code "86") (name "unconnected-(EXP1-Pad9)") (class "Default")
      (node (ref "EXP1") (pin "9") (pinfunction "9_9") (pintype "passive"))
    )
    (net (code "87") (name "unconnected-(U5-Y4-Pad11)") (class "Default")
      (node (ref "U5") (pin "11") (pinfunction "Y4_11") (pintype "bidirectional"))
    )
    (net (code "88") (name "unconnected-(U5-Y5-Pad10)") (class "Default")
      (node (ref "U5") (pin "10") (pinfunction "Y5_10") (pintype "bidirectional"))
    )
    (net (code "89") (name "unconnected-(U5-Y6-Pad9)") (class "Default")
      (node (ref "U5") (pin "9") (pinfunction "Y6_9") (pintype "bidirectional"))
    )
    (net (code "90") (name "unconnected-(U5-Y7-Pad7)") (class "Default")
      (node (ref "U5") (pin "7") (pinfunction "Y7_7") (pintype "bidirectional"))
    )
  )
)
